# Receive.net
KiCad netlist of a schematic drawn in Altium Designer
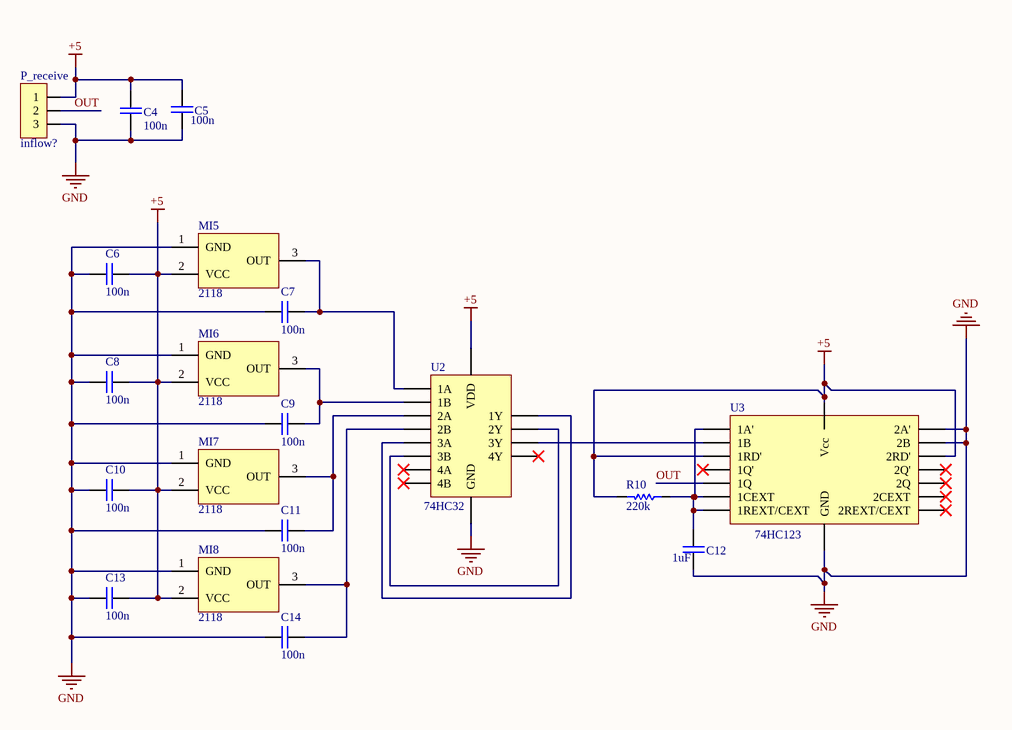
[diagram p0: Receive.SchDoc]

(export (version "E")
  (design (tool "Eeschema 10.0.6"))
  (components
    (comp (ref "C4")
      (value "100n")
      (footprint "CAP 1206/3216")
      (description "Bipolar ceramic capacitor SMD")
      (fields (field (name "VALIDATION") "Valid"))
      (libsource (lib "aKaReZa") (part "Cap_Multi_SMD_1206"))
    )
    (comp (ref "C5")
      (value "100n")
      (footprint "CAP 1206/3216")
      (description "Bipolar ceramic capacitor SMD")
      (fields (field (name "VALIDATION") "Valid"))
      (libsource (lib "aKaReZa") (part "Cap_Multi_SMD_1206"))
    )
    (comp (ref "C6")
      (value "100n")
      (footprint "CAP 1206/3216")
      (description "Bipolar ceramic capacitor SMD")
      (fields (field (name "VALIDATION") "Valid"))
      (libsource (lib "aKaReZa") (part "Cap_Multi_SMD_1206"))
    )
    (comp (ref "C7")
      (value "100n")
      (footprint "CAP 1206/3216")
      (description "Bipolar ceramic capacitor SMD")
      (fields (field (name "VALIDATION") "Valid"))
      (libsource (lib "aKaReZa") (part "Cap_Multi_SMD_1206"))
    )
    (comp (ref "C8")
      (value "100n")
      (footprint "CAP 1206/3216")
      (description "Bipolar ceramic capacitor SMD")
      (fields (field (name "VALIDATION") "Valid"))
      (libsource (lib "aKaReZa") (part "Cap_Multi_SMD_1206"))
    )
    (comp (ref "C9")
      (value "100n")
      (footprint "CAP 1206/3216")
      (description "Bipolar ceramic capacitor SMD")
      (fields (field (name "VALIDATION") "Valid"))
      (libsource (lib "aKaReZa") (part "Cap_Multi_SMD_1206"))
    )
    (comp (ref "C10")
      (value "100n")
      (footprint "CAP 1206/3216")
      (description "Bipolar ceramic capacitor SMD")
      (fields (field (name "VALIDATION") "Valid"))
      (libsource (lib "aKaReZa") (part "Cap_Multi_SMD_1206"))
    )
    (comp (ref "C11")
      (value "100n")
      (footprint "CAP 1206/3216")
      (description "Bipolar ceramic capacitor SMD")
      (fields (field (name "VALIDATION") "Valid"))
      (libsource (lib "aKaReZa") (part "Cap_Multi_SMD_1206"))
    )
    (comp (ref "C12")
      (value "1uF")
      (footprint "CAP 1206/3216")
      (description "Bipolar ceramic capacitor SMD")
      (fields (field (name "VALIDATION") "Valid"))
      (libsource (lib "aKaReZa") (part "Cap_Multi_SMD_1206"))
    )
    (comp (ref "C13")
      (value "100n")
      (footprint "CAP 1206/3216")
      (description "Bipolar ceramic capacitor SMD")
      (fields (field (name "VALIDATION") "Valid"))
      (libsource (lib "aKaReZa") (part "Cap_Multi_SMD_1206"))
    )
    (comp (ref "C14")
      (value "100n")
      (footprint "CAP 1206/3216")
      (description "Bipolar ceramic capacitor SMD")
      (fields (field (name "VALIDATION") "Valid"))
      (libsource (lib "aKaReZa") (part "Cap_Multi_SMD_1206"))
    )
    (comp (ref "MI5")
      (value "TSOP1138")
      (footprint "TSOP1238")
      (description "Reciver Remot Control (IR) 30-56KHz")
      (fields (field (name "INFLOW") "2118") (field (name "VALIDATION") "NT"))
      (libsource (lib "aKaReZa") (part "ModSen_IR_TSOP1138"))
    )
    (comp (ref "MI6")
      (value "TSOP1138")
      (footprint "TSOP1238")
      (description "Reciver Remot Control (IR) 30-56KHz")
      (fields (field (name "INFLOW") "2118") (field (name "VALIDATION") "NT"))
      (libsource (lib "aKaReZa") (part "ModSen_IR_TSOP1138"))
    )
    (comp (ref "MI7")
      (value "TSOP1138")
      (footprint "TSOP1238")
      (description "Reciver Remot Control (IR) 30-56KHz")
      (fields (field (name "INFLOW") "2118") (field (name "VALIDATION") "NT"))
      (libsource (lib "aKaReZa") (part "ModSen_IR_TSOP1138"))
    )
    (comp (ref "MI8")
      (value "TSOP1138")
      (footprint "TSOP1238")
      (description "Reciver Remot Control (IR) 30-56KHz")
      (fields (field (name "INFLOW") "2118") (field (name "VALIDATION") "NT"))
      (libsource (lib "aKaReZa") (part "ModSen_IR_TSOP1138"))
    )
    (comp (ref "P_receive")
      (value "3'Pin")
      (footprint "MOLEX KK 0022272031")
      (description "Signal Connector 3'Pin")
      (fields (field (name "INFLOW") "inflow?") (field (name "VALIDATION") "Valid"))
      (libsource (lib "aKaReZa") (part "Con_Signal_3"))
    )
    (comp (ref "R10")
      (value "220k")
      (footprint "RES 1206 (3216X08L)")
      (description "Resistor")
      (fields (field (name "VALIDATION") "Valid"))
      (libsource (lib "aKaReZa") (part "Res_SMD_1206"))
    )
    (comp (ref "U2")
      (value "74HC32")
      (footprint "SOIC-14")
      (description "Quadruple 2-Input Positive OR Gate")
      (libsource (lib "my-lib") (part "74HC32"))
    )
    (comp (ref "U3")
      (value "74HC123")
      (footprint "SOIC-16")
      (description "Dual retriggerable monostable multivibrator with reset")
      (libsource (lib "my-lib") (part "74HC123"))
    )
  )
  (nets
    (net (code "1") (name "+5") (class "Default")
      (node (ref "C10") (pin "1") (pinfunction "1_1") (pintype "passive"))
      (node (ref "C13") (pin "1") (pinfunction "1_1") (pintype "passive"))
      (node (ref "C4") (pin "1") (pinfunction "1_1") (pintype "passive"))
      (node (ref "C5") (pin "1") (pinfunction "1_1") (pintype "passive"))
      (node (ref "C6") (pin "1") (pinfunction "1_1") (pintype "passive"))
      (node (ref "C8") (pin "1") (pinfunction "1_1") (pintype "passive"))
      (node (ref "MI5") (pin "2") (pinfunction "VCC_2") (pintype "passive"))
      (node (ref "MI6") (pin "2") (pinfunction "VCC_2") (pintype "passive"))
      (node (ref "MI7") (pin "2") (pinfunction "VCC_2") (pintype "passive"))
      (node (ref "MI8") (pin "2") (pinfunction "VCC_2") (pintype "passive"))
      (node (ref "P_receive") (pin "1") (pinfunction "1_1") (pintype "passive"))
      (node (ref "R10") (pin "2") (pinfunction "2_2") (pintype "passive"))
      (node (ref "U2") (pin "14") (pinfunction "VDD_14") (pintype "passive"))
      (node (ref "U3") (pin "10") (pinfunction "2RD'_10") (pintype "passive"))
      (node (ref "U3") (pin "15") (pinfunction "Vcc_15") (pintype "passive"))
      (node (ref "U3") (pin "2") (pinfunction "1RD'_2") (pintype "passive"))
    )
    (net (code "2") (name "/OUT") (class "Default")
      (node (ref "P_receive") (pin "2") (pinfunction "2_2") (pintype "passive"))
      (node (ref "U3") (pin "12") (pinfunction "1Q_12") (pintype "passive"))
    )
    (net (code "3") (name "GND") (class "Default")
      (node (ref "C10") (pin "2") (pinfunction "2_2") (pintype "passive"))
      (node (ref "C11") (pin "1") (pinfunction "1_1") (pintype "passive"))
      (node (ref "C12") (pin "2") (pinfunction "2_2") (pintype "passive"))
      (node (ref "C13") (pin "2") (pinfunction "2_2") (pintype "passive"))
      (node (ref "C14") (pin "1") (pinfunction "1_1") (pintype "passive"))
      (node (ref "C4") (pin "2") (pinfunction "2_2") (pintype "passive"))
      (node (ref "C5") (pin "2") (pinfunction "2_2") (pintype "passive"))
      (node (ref "C6") (pin "2") (pinfunction "2_2") (pintype "passive"))
      (node (ref "C7") (pin "1") (pinfunction "1_1") (pintype "passive"))
      (node (ref "C8") (pin "2") (pinfunction "2_2") (pintype "passive"))
      (node (ref "C9") (pin "2") (pinfunction "2_2") (pintype "passive"))
      (node (ref "MI5") (pin "1") (pinfunction "GND_1") (pintype "passive"))
      (node (ref "MI6") (pin "1") (pinfunction "GND_1") (pintype "passive"))
      (node (ref "MI7") (pin "1") (pinfunction "GND_1") (pintype "passive"))
      (node (ref "MI8") (pin "1") (pinfunction "GND_1") (pintype "passive"))
      (node (ref "P_receive") (pin "3") (pinfunction "3_3") (pintype "passive"))
      (node (ref "U2") (pin "7") (pinfunction "GND_7") (pintype "passive"))
      (node (ref "U3") (pin "7") (pinfunction "GND_7") (pintype "passive"))
      (node (ref "U3") (pin "8") (pinfunction "2A'_8") (pintype "passive"))
      (node (ref "U3") (pin "9") (pinfunction "2B_9") (pintype "passive"))
    )
    (net (code "4") (name "Net-(MI5-OUT)") (class "Default")
      (node (ref "C7") (pin "2") (pinfunction "2_2") (pintype "passive"))
      (node (ref "MI5") (pin "3") (pinfunction "OUT_3") (pintype "passive"))
      (node (ref "U2") (pin "1") (pinfunction "1A_1") (pintype "passive"))
    )
    (net (code "5") (name "Net-(MI6-OUT)") (class "Default")
      (node (ref "C9") (pin "1") (pinfunction "1_1") (pintype "passive"))
      (node (ref "MI6") (pin "3") (pinfunction "OUT_3") (pintype "passive"))
      (node (ref "U2") (pin "2") (pinfunction "1B_2") (pintype "passive"))
    )
    (net (code "6") (name "Net-(MI7-OUT)") (class "Default")
      (node (ref "C11") (pin "2") (pinfunction "2_2") (pintype "passive"))
      (node (ref "MI7") (pin "3") (pinfunction "OUT_3") (pintype "passive"))
      (node (ref "U2") (pin "4") (pinfunction "2A_4") (pintype "passive"))
    )
    (net (code "7") (name "Net-(MI8-OUT)") (class "Default")
      (node (ref "C14") (pin "2") (pinfunction "2_2") (pintype "passive"))
      (node (ref "MI8") (pin "3") (pinfunction "OUT_3") (pintype "passive"))
      (node (ref "U2") (pin "5") (pinfunction "2B_5") (pintype "passive"))
    )
    (net (code "8") (name "Net-(U2-1Y)") (class "Default")
      (node (ref "U2") (pin "3") (pinfunction "1Y_3") (pintype "passive"))
      (node (ref "U2") (pin "9") (pinfunction "3A_9") (pintype "passive"))
    )
    (net (code "9") (name "Net-(U2-2Y)") (class "Default")
      (node (ref "U2") (pin "10") (pinfunction "3B_10") (pintype "passive"))
      (node (ref "U2") (pin "6") (pinfunction "2Y_6") (pintype "passive"))
    )
    (net (code "10") (name "Net-(U2-3Y)") (class "Default")
      (node (ref "U2") (pin "8") (pinfunction "3Y_8") (pintype "passive"))
      (node (ref "U3") (pin "1") (pinfunction "1B_1") (pintype "passive"))
    )
    (net (code "11") (name "Net-(U3-1A')") (class "Default")
      (node (ref "C12") (pin "1") (pinfunction "1_1") (pintype "passive"))
      (node (ref "R10") (pin "1") (pinfunction "1_1") (pintype "passive"))
      (node (ref "U3") (pin "0") (pinfunction "1A'_0") (pintype "passive"))
      (node (ref "U3") (pin "13") (pinfunction "1CEXT_13") (pintype "passive"))
      (node (ref "U3") (pin "14") (pinfunction "1REXT/CEXT_14") (pintype "passive"))
    )
    (net (code "12") (name "unconnected-(U2-4A-Pad12)") (class "Default")
      (node (ref "U2") (pin "12") (pinfunction "4A_12") (pintype "passive+no_connect"))
    )
    (net (code "13") (name "unconnected-(U2-4B-Pad13)") (class "Default")
      (node (ref "U2") (pin "13") (pinfunction "4B_13") (pintype "passive+no_connect"))
    )
    (net (code "14") (name "unconnected-(U2-4Y-Pad11)") (class "Default")
      (node (ref "U2") (pin "11") (pinfunction "4Y_11") (pintype "passive+no_connect"))
    )
    (net (code "15") (name "unconnected-(U3-1Q'-Pad3)") (class "Default")
      (node (ref "U3") (pin "3") (pinfunction "1Q'_3") (pintype "passive+no_connect"))
    )
    (net (code "16") (name "unconnected-(U3-2CEXT-Pad5)") (class "Default")
      (node (ref "U3") (pin "5") (pinfunction "2CEXT_5") (pintype "passive+no_connect"))
    )
    (net (code "17") (name "unconnected-(U3-2Q'-Pad11)") (class "Default")
      (node (ref "U3") (pin "11") (pinfunction "2Q'_11") (pintype "passive+no_connect"))
    )
    (net (code "18") (name "unconnected-(U3-2Q-Pad4)") (class "Default")
      (node (ref "U3") (pin "4") (pinfunction "2Q_4") (pintype "passive+no_connect"))
    )
    (net (code "19") (name "unconnected-(U3-2REXT{slash}CEXT-Pad6)") (class "Default")
      (node (ref "U3") (pin "6") (pinfunction "2REXT/CEXT_6") (pintype "passive+no_connect"))
    )
  )
)
